# noise-and-ring-modulator-v1_0.net
KiCad netlist of a schematic drawn in EAGLE
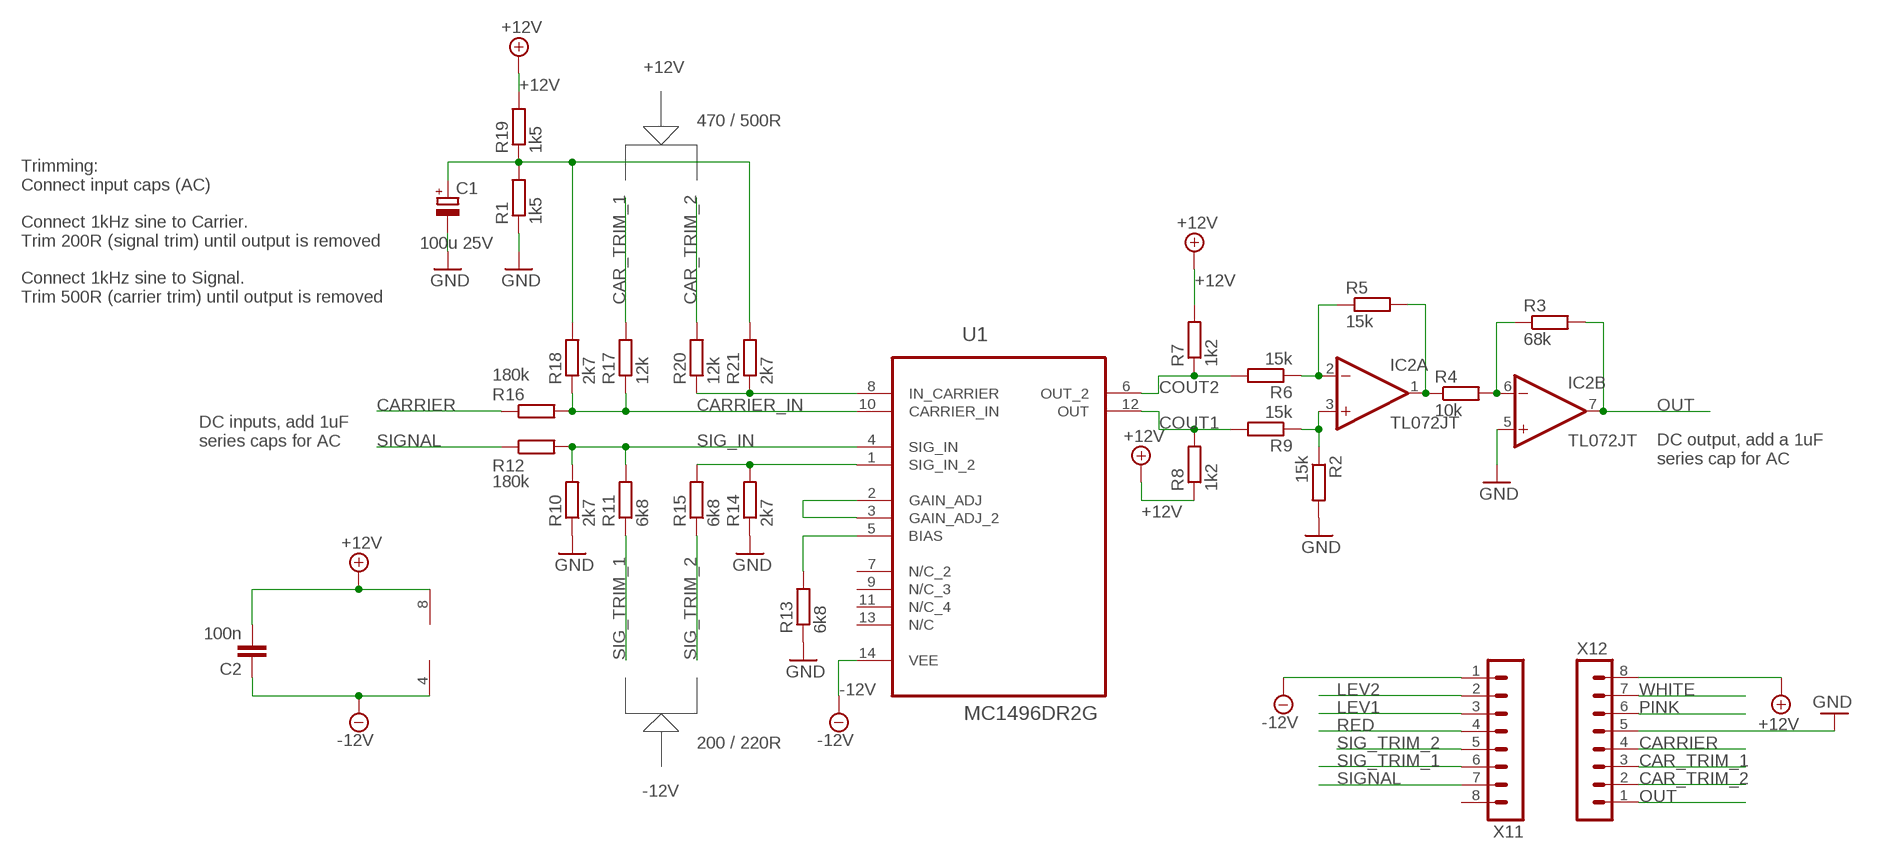
[diagram p0: schematic, sheet 1]
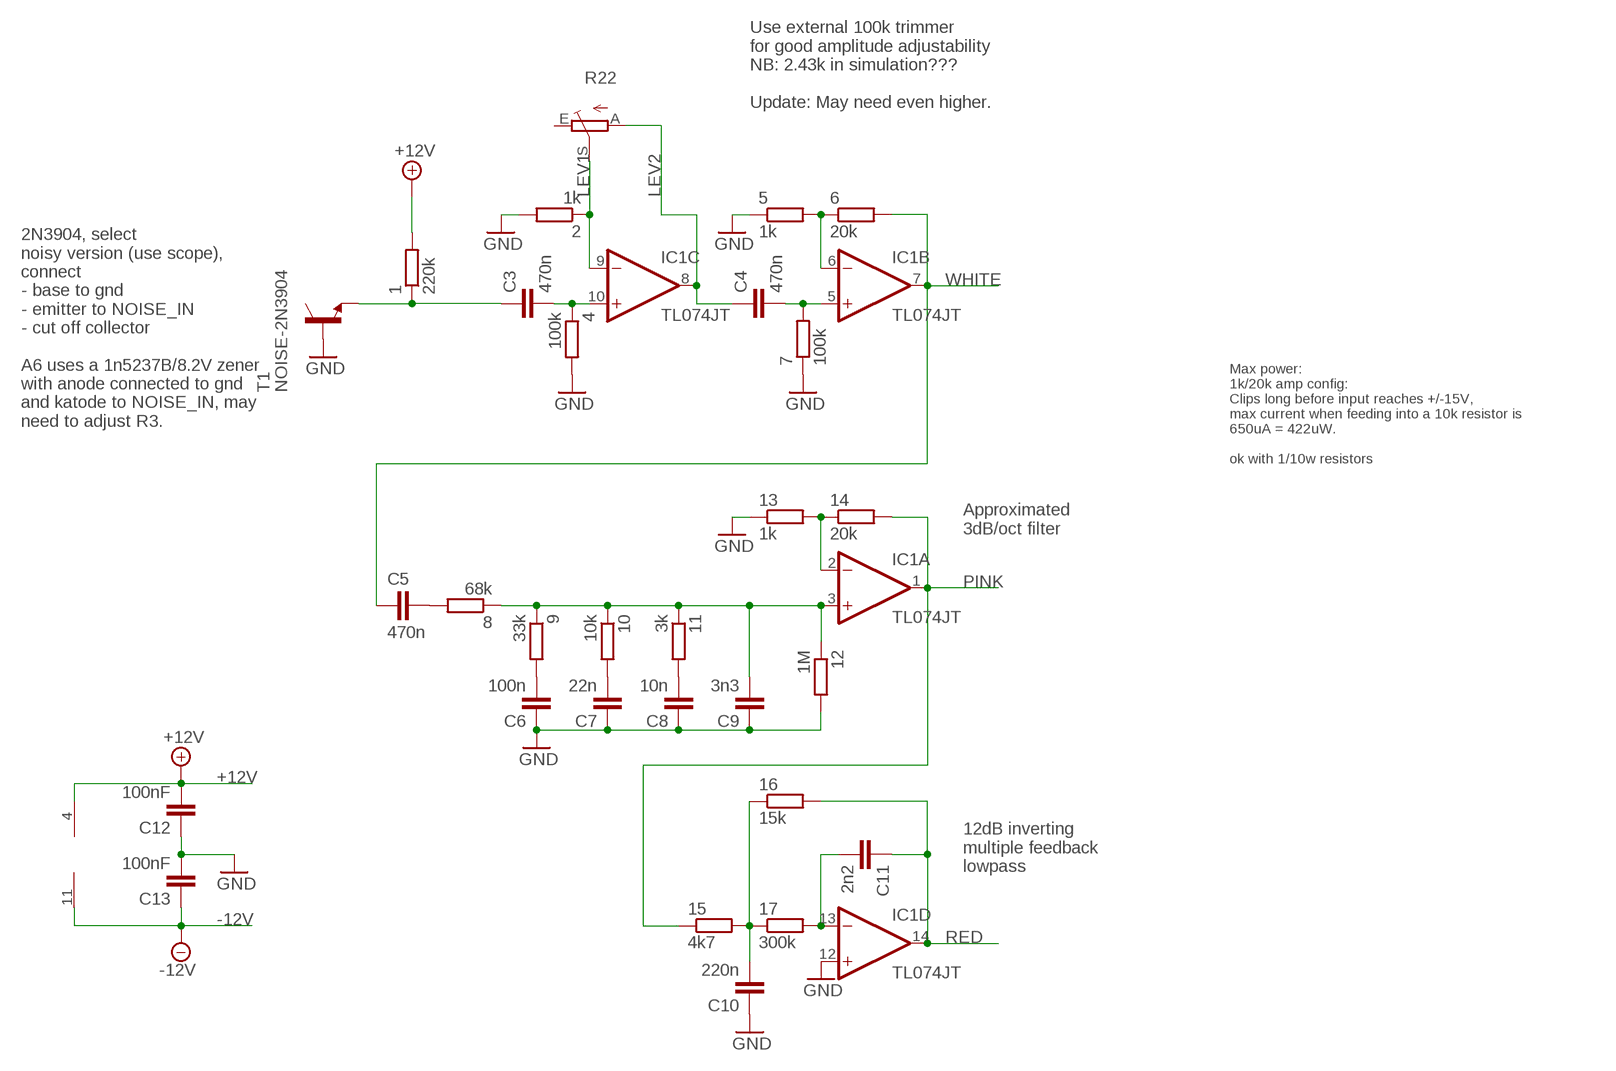
[diagram p1: schematic, sheet 2]

(export (version "E")
  (design (tool "Eeschema 10.0.6"))
  (components
    (comp (ref "1")
      (value "220k")
      (footprint "eagle-import:R0402")
      (libsource (lib "eagle-import") (part "R-EU_R0402"))
    )
    (comp (ref "2")
      (value "1k")
      (footprint "eagle-import:R0402")
      (libsource (lib "eagle-import") (part "R-EU_R0402"))
    )
    (comp (ref "4")
      (value "100k")
      (footprint "eagle-import:R0402")
      (libsource (lib "eagle-import") (part "R-EU_R0402"))
    )
    (comp (ref "5")
      (value "1k")
      (footprint "eagle-import:R0402")
      (libsource (lib "eagle-import") (part "R-EU_R0402"))
    )
    (comp (ref "6")
      (value "20k")
      (footprint "eagle-import:R0402")
      (libsource (lib "eagle-import") (part "R-EU_R0402"))
    )
    (comp (ref "7")
      (value "100k")
      (footprint "eagle-import:R0402")
      (libsource (lib "eagle-import") (part "R-EU_R0402"))
    )
    (comp (ref "8")
      (value "68k")
      (footprint "eagle-import:R0402")
      (libsource (lib "eagle-import") (part "R-EU_R0402"))
    )
    (comp (ref "9")
      (value "33k")
      (footprint "eagle-import:R0402")
      (libsource (lib "eagle-import") (part "R-EU_R0402"))
    )
    (comp (ref "10")
      (value "10k")
      (footprint "eagle-import:R0402")
      (libsource (lib "eagle-import") (part "R-EU_R0402"))
    )
    (comp (ref "11")
      (value "3k")
      (footprint "eagle-import:R0402")
      (libsource (lib "eagle-import") (part "R-EU_R0402"))
    )
    (comp (ref "12")
      (value "1M")
      (footprint "eagle-import:R0402")
      (libsource (lib "eagle-import") (part "R-EU_R0402"))
    )
    (comp (ref "13")
      (value "1k")
      (footprint "eagle-import:R0402")
      (libsource (lib "eagle-import") (part "R-EU_R0402"))
    )
    (comp (ref "14")
      (value "20k")
      (footprint "eagle-import:R0402")
      (libsource (lib "eagle-import") (part "R-EU_R0402"))
    )
    (comp (ref "15")
      (value "4k7")
      (footprint "eagle-import:R0402")
      (libsource (lib "eagle-import") (part "R-EU_R0402"))
    )
    (comp (ref "16")
      (value "15k")
      (footprint "eagle-import:R0402")
      (libsource (lib "eagle-import") (part "R-EU_R0402"))
    )
    (comp (ref "17")
      (value "300k")
      (footprint "eagle-import:R0402")
      (libsource (lib "eagle-import") (part "R-EU_R0402"))
    )
    (comp (ref "C3")
      (value "470n")
      (footprint "eagle-import:C0402-J")
      (libsource (lib "eagle-import") (part "C-EU-J"))
    )
    (comp (ref "C4")
      (value "470n")
      (footprint "eagle-import:C0402-J")
      (libsource (lib "eagle-import") (part "C-EU-J"))
    )
    (comp (ref "C5")
      (value "470n")
      (footprint "eagle-import:C0402-J")
      (libsource (lib "eagle-import") (part "C-EU-J"))
    )
    (comp (ref "C6")
      (value "100n")
      (footprint "eagle-import:C0402-J")
      (libsource (lib "eagle-import") (part "C-EU-J"))
    )
    (comp (ref "C7")
      (value "22n")
      (footprint "eagle-import:C0402-J")
      (libsource (lib "eagle-import") (part "C-EU-J"))
    )
    (comp (ref "C8")
      (value "10n")
      (footprint "eagle-import:C0402-J")
      (libsource (lib "eagle-import") (part "C-EU-J"))
    )
    (comp (ref "C9")
      (value "3n3")
      (footprint "eagle-import:C0402-J")
      (libsource (lib "eagle-import") (part "C-EU-J"))
    )
    (comp (ref "C10")
      (value "220n")
      (footprint "eagle-import:C0402-J")
      (libsource (lib "eagle-import") (part "C-EU-J"))
    )
    (comp (ref "C11")
      (value "2n2")
      (footprint "eagle-import:C0402-J")
      (libsource (lib "eagle-import") (part "C-EU-J"))
    )
    (comp (ref "C12")
      (value "100nF")
      (footprint "eagle-import:C0402-J")
      (libsource (lib "eagle-import") (part "C-EU-J"))
    )
    (comp (ref "C13")
      (value "100nF")
      (footprint "eagle-import:C0402-J")
      (libsource (lib "eagle-import") (part "C-EU-J"))
    )
    (comp (ref "IC1")
      (value "TL074JT")
      (footprint "eagle-import:TSSOP14J")
      (libsource (lib "eagle-import") (part "TL074JT"))
    )
    (comp (ref "R22")
      (value "TRIM_EU-S64W")
      (footprint "eagle-import:S64W")
      (libsource (lib "eagle-import") (part "TRIM_EU-S64W"))
    )
    (comp (ref "T1")
      (value "NOISE-2N3904")
      (footprint "eagle-import:NOISE-2N3904-J")
      (libsource (lib "eagle-import") (part "NOISE-2N3904"))
    )
    (comp (ref "C1")
      (value "100u 25V")
      (footprint "eagle-import:UD-4X5,8_NICHICON")
      (libsource (lib "eagle-import") (part "CPOL-EUUD-4X5,8"))
    )
    (comp (ref "C2")
      (value "100n")
      (footprint "eagle-import:C0402-J")
      (libsource (lib "eagle-import") (part "C-EU-J"))
    )
    (comp (ref "IC2")
      (value "TL072JT")
      (footprint "eagle-import:TSSOP8J")
      (libsource (lib "eagle-import") (part "TL072JT"))
    )
    (comp (ref "R1")
      (value "1k5")
      (footprint "eagle-import:R0402")
      (libsource (lib "eagle-import") (part "R-EU_R0402"))
    )
    (comp (ref "R2")
      (value "15k")
      (footprint "eagle-import:R0402")
      (libsource (lib "eagle-import") (part "R-EU_R0402"))
    )
    (comp (ref "R3")
      (value "68k")
      (footprint "eagle-import:R0402")
      (libsource (lib "eagle-import") (part "R-EU_R0402"))
    )
    (comp (ref "R4")
      (value "10k")
      (footprint "eagle-import:R0402")
      (libsource (lib "eagle-import") (part "R-EU_R0402"))
    )
    (comp (ref "R5")
      (value "15k")
      (footprint "eagle-import:R0402")
      (libsource (lib "eagle-import") (part "R-EU_R0402"))
    )
    (comp (ref "R6")
      (value "15k")
      (footprint "eagle-import:R0402")
      (libsource (lib "eagle-import") (part "R-EU_R0402"))
    )
    (comp (ref "R7")
      (value "1k2")
      (footprint "eagle-import:R0402")
      (libsource (lib "eagle-import") (part "R-EU_R0402"))
    )
    (comp (ref "R8")
      (value "1k2")
      (footprint "eagle-import:R0402")
      (libsource (lib "eagle-import") (part "R-EU_R0402"))
    )
    (comp (ref "R9")
      (value "15k")
      (footprint "eagle-import:R0402")
      (libsource (lib "eagle-import") (part "R-EU_R0402"))
    )
    (comp (ref "R10")
      (value "2k7")
      (footprint "eagle-import:R0402")
      (libsource (lib "eagle-import") (part "R-EU_R0402"))
    )
    (comp (ref "R11")
      (value "6k8")
      (footprint "eagle-import:R0402")
      (libsource (lib "eagle-import") (part "R-EU_R0402"))
    )
    (comp (ref "R12")
      (value "180k")
      (footprint "eagle-import:R0402")
      (libsource (lib "eagle-import") (part "R-EU_R0402"))
    )
    (comp (ref "R13")
      (value "6k8")
      (footprint "eagle-import:R0402")
      (libsource (lib "eagle-import") (part "R-EU_R0402"))
    )
    (comp (ref "R14")
      (value "2k7")
      (footprint "eagle-import:R0402")
      (libsource (lib "eagle-import") (part "R-EU_R0402"))
    )
    (comp (ref "R15")
      (value "6k8")
      (footprint "eagle-import:R0402")
      (libsource (lib "eagle-import") (part "R-EU_R0402"))
    )
    (comp (ref "R16")
      (value "180k")
      (footprint "eagle-import:R0402")
      (libsource (lib "eagle-import") (part "R-EU_R0402"))
    )
    (comp (ref "R17")
      (value "12k")
      (footprint "eagle-import:R0402")
      (libsource (lib "eagle-import") (part "R-EU_R0402"))
    )
    (comp (ref "R18")
      (value "2k7")
      (footprint "eagle-import:R0402")
      (libsource (lib "eagle-import") (part "R-EU_R0402"))
    )
    (comp (ref "R19")
      (value "1k5")
      (footprint "eagle-import:R0402")
      (libsource (lib "eagle-import") (part "R-EU_R0402"))
    )
    (comp (ref "R20")
      (value "12k")
      (footprint "eagle-import:R0402")
      (libsource (lib "eagle-import") (part "R-EU_R0402"))
    )
    (comp (ref "R21")
      (value "2k7")
      (footprint "eagle-import:R0402")
      (libsource (lib "eagle-import") (part "R-EU_R0402"))
    )
    (comp (ref "U1")
      (value "MC1496DR2G")
      (footprint "eagle-import:SOIC127P600X175-14N")
      (libsource (lib "eagle-import") (part "MC1496DR2G"))
    )
    (comp (ref "X11")
      (value "MA08-1JN")
      (footprint "eagle-import:MA08N-1J")
      (libsource (lib "eagle-import") (part "MA08-1JN"))
    )
    (comp (ref "X12")
      (value "MA08-1JN")
      (footprint "eagle-import:MA08N-1J")
      (libsource (lib "eagle-import") (part "MA08-1JN"))
    )
  )
  (nets
    (net (code "1") (name "+12V") (class "Default")
      (node (ref "1") (pin "2") (pinfunction "2_2") (pintype "passive"))
      (node (ref "C12") (pin "2") (pinfunction "2_2") (pintype "passive"))
      (node (ref "C2") (pin "2") (pinfunction "2_2") (pintype "passive"))
      (node (ref "IC1") (pin "4") (pinfunction "V+_4") (pintype "power_in"))
      (node (ref "IC2") (pin "8") (pinfunction "V+_8") (pintype "power_in"))
      (node (ref "R19") (pin "2") (pinfunction "2_2") (pintype "passive"))
      (node (ref "R7") (pin "2") (pinfunction "2_2") (pintype "passive"))
      (node (ref "R8") (pin "1") (pinfunction "1_1") (pintype "passive"))
      (node (ref "X12") (pin "8") (pinfunction "8_8") (pintype "passive"))
    )
    (net (code "2") (name "-12V") (class "Default")
      (node (ref "C13") (pin "1") (pinfunction "1_1") (pintype "passive"))
      (node (ref "C2") (pin "1") (pinfunction "1_1") (pintype "passive"))
      (node (ref "IC1") (pin "11") (pinfunction "V-_11") (pintype "power_in"))
      (node (ref "IC2") (pin "4") (pinfunction "V-_4") (pintype "power_in"))
      (node (ref "U1") (pin "14") (pinfunction "VEE_14") (pintype "passive"))
      (node (ref "X11") (pin "1") (pinfunction "1_1") (pintype "passive"))
    )
    (net (code "3") (name "CARRIER") (class "Default")
      (node (ref "R16") (pin "1") (pinfunction "1_1") (pintype "passive"))
      (node (ref "X12") (pin "4") (pinfunction "4_4") (pintype "passive"))
    )
    (net (code "4") (name "CARRIER_IN") (class "Default")
      (node (ref "R16") (pin "2") (pinfunction "2_2") (pintype "passive"))
      (node (ref "R17") (pin "1") (pinfunction "1_1") (pintype "passive"))
      (node (ref "R18") (pin "1") (pinfunction "1_1") (pintype "passive"))
      (node (ref "U1") (pin "10") (pinfunction "CARRIER_IN_10") (pintype "power_in"))
    )
    (net (code "5") (name "CAR_TRIM_1") (class "Default")
      (node (ref "R17") (pin "2") (pinfunction "2_2") (pintype "passive"))
      (node (ref "X12") (pin "3") (pinfunction "3_3") (pintype "passive"))
    )
    (net (code "6") (name "CAR_TRIM_2") (class "Default")
      (node (ref "R20") (pin "2") (pinfunction "2_2") (pintype "passive"))
      (node (ref "X12") (pin "2") (pinfunction "2_2") (pintype "passive"))
    )
    (net (code "7") (name "COUT1") (class "Default")
      (node (ref "R8") (pin "2") (pinfunction "2_2") (pintype "passive"))
      (node (ref "R9") (pin "2") (pinfunction "2_2") (pintype "passive"))
      (node (ref "U1") (pin "12") (pinfunction "OUT_12") (pintype "output"))
    )
    (net (code "8") (name "COUT2") (class "Default")
      (node (ref "R6") (pin "2") (pinfunction "2_2") (pintype "passive"))
      (node (ref "R7") (pin "1") (pinfunction "1_1") (pintype "passive"))
      (node (ref "U1") (pin "6") (pinfunction "OUT_2_6") (pintype "output"))
    )
    (net (code "9") (name "GND") (class "Default")
      (node (ref "12") (pin "2") (pinfunction "2_2") (pintype "passive"))
      (node (ref "13") (pin "1") (pinfunction "1_1") (pintype "passive"))
      (node (ref "2") (pin "2") (pinfunction "2_2") (pintype "passive"))
      (node (ref "4") (pin "2") (pinfunction "2_2") (pintype "passive"))
      (node (ref "5") (pin "1") (pinfunction "1_1") (pintype "passive"))
      (node (ref "7") (pin "1") (pinfunction "1_1") (pintype "passive"))
      (node (ref "C1") (pin "-") (pinfunction "-_-") (pintype "passive"))
      (node (ref "C10") (pin "1") (pinfunction "1_1") (pintype "passive"))
      (node (ref "C12") (pin "1") (pinfunction "1_1") (pintype "passive"))
      (node (ref "C13") (pin "2") (pinfunction "2_2") (pintype "passive"))
      (node (ref "C6") (pin "1") (pinfunction "1_1") (pintype "passive"))
      (node (ref "C7") (pin "1") (pinfunction "1_1") (pintype "passive"))
      (node (ref "C8") (pin "1") (pinfunction "1_1") (pintype "passive"))
      (node (ref "C9") (pin "1") (pinfunction "1_1") (pintype "passive"))
      (node (ref "IC1") (pin "12") (pinfunction "+IN_12") (pintype "input"))
      (node (ref "IC2") (pin "5") (pinfunction "+IN_5") (pintype "input"))
      (node (ref "R1") (pin "1") (pinfunction "1_1") (pintype "passive"))
      (node (ref "R10") (pin "1") (pinfunction "1_1") (pintype "passive"))
      (node (ref "R13") (pin "1") (pinfunction "1_1") (pintype "passive"))
      (node (ref "R14") (pin "1") (pinfunction "1_1") (pintype "passive"))
      (node (ref "R2") (pin "2") (pinfunction "2_2") (pintype "passive"))
      (node (ref "T1") (pin "B") (pinfunction "B_B") (pintype "passive"))
      (node (ref "X12") (pin "5") (pinfunction "5_5") (pintype "passive"))
    )
    (net (code "10") (name "LEV1") (class "Default")
      (node (ref "2") (pin "1") (pinfunction "1_1") (pintype "passive"))
      (node (ref "IC1") (pin "9") (pinfunction "-IN_9") (pintype "input"))
      (node (ref "R22") (pin "S") (pinfunction "S_S") (pintype "passive"))
      (node (ref "X11") (pin "3") (pinfunction "3_3") (pintype "passive"))
    )
    (net (code "11") (name "LEV2") (class "Default")
      (node (ref "C4") (pin "1") (pinfunction "1_1") (pintype "passive"))
      (node (ref "IC1") (pin "8") (pinfunction "OUT_8") (pintype "output"))
      (node (ref "R22") (pin "A") (pinfunction "A_A") (pintype "passive"))
      (node (ref "X11") (pin "2") (pinfunction "2_2") (pintype "passive"))
    )
    (net (code "12") (name "Net-(1-Pad1)") (class "Default")
      (node (ref "1") (pin "1") (pinfunction "1_1") (pintype "passive"))
      (node (ref "C3") (pin "1") (pinfunction "1_1") (pintype "passive"))
      (node (ref "T1") (pin "E") (pinfunction "E_E") (pintype "passive"))
    )
    (net (code "13") (name "Net-(8-Pad2)") (class "Default")
      (node (ref "8") (pin "2") (pinfunction "2_2") (pintype "passive"))
      (node (ref "C5") (pin "2") (pinfunction "2_2") (pintype "passive"))
    )
    (net (code "14") (name "Net-(9-Pad2)") (class "Default")
      (node (ref "9") (pin "2") (pinfunction "2_2") (pintype "passive"))
      (node (ref "C6") (pin "2") (pinfunction "2_2") (pintype "passive"))
    )
    (net (code "15") (name "Net-(10-Pad2)") (class "Default")
      (node (ref "10") (pin "2") (pinfunction "2_2") (pintype "passive"))
      (node (ref "C7") (pin "2") (pinfunction "2_2") (pintype "passive"))
    )
    (net (code "16") (name "Net-(11-Pad2)") (class "Default")
      (node (ref "11") (pin "2") (pinfunction "2_2") (pintype "passive"))
      (node (ref "C8") (pin "2") (pinfunction "2_2") (pintype "passive"))
    )
    (net (code "17") (name "Net-(15-Pad2)") (class "Default")
      (node (ref "15") (pin "2") (pinfunction "2_2") (pintype "passive"))
      (node (ref "16") (pin "1") (pinfunction "1_1") (pintype "passive"))
      (node (ref "17") (pin "1") (pinfunction "1_1") (pintype "passive"))
      (node (ref "C10") (pin "2") (pinfunction "2_2") (pintype "passive"))
    )
    (net (code "18") (name "Net-(C1-Pad+)") (class "Default")
      (node (ref "C1") (pin "+") (pinfunction "+_+") (pintype "passive"))
      (node (ref "R1") (pin "2") (pinfunction "2_2") (pintype "passive"))
      (node (ref "R18") (pin "2") (pinfunction "2_2") (pintype "passive"))
      (node (ref "R19") (pin "1") (pinfunction "1_1") (pintype "passive"))
      (node (ref "R21") (pin "2") (pinfunction "2_2") (pintype "passive"))
    )
    (net (code "19") (name "Net-(IC1A-+IN)") (class "Default")
      (node (ref "10") (pin "1") (pinfunction "1_1") (pintype "passive"))
      (node (ref "11") (pin "1") (pinfunction "1_1") (pintype "passive"))
      (node (ref "12") (pin "1") (pinfunction "1_1") (pintype "passive"))
      (node (ref "8") (pin "1") (pinfunction "1_1") (pintype "passive"))
      (node (ref "9") (pin "1") (pinfunction "1_1") (pintype "passive"))
      (node (ref "C9") (pin "2") (pinfunction "2_2") (pintype "passive"))
      (node (ref "IC1") (pin "3") (pinfunction "+IN_3") (pintype "input"))
    )
    (net (code "20") (name "Net-(IC1A--IN)") (class "Default")
      (node (ref "13") (pin "2") (pinfunction "2_2") (pintype "passive"))
      (node (ref "14") (pin "1") (pinfunction "1_1") (pintype "passive"))
      (node (ref "IC1") (pin "2") (pinfunction "-IN_2") (pintype "input"))
    )
    (net (code "21") (name "Net-(IC1B-+IN)") (class "Default")
      (node (ref "7") (pin "2") (pinfunction "2_2") (pintype "passive"))
      (node (ref "C4") (pin "2") (pinfunction "2_2") (pintype "passive"))
      (node (ref "IC1") (pin "5") (pinfunction "+IN_5") (pintype "input"))
    )
    (net (code "22") (name "Net-(IC1B--IN)") (class "Default")
      (node (ref "5") (pin "2") (pinfunction "2_2") (pintype "passive"))
      (node (ref "6") (pin "1") (pinfunction "1_1") (pintype "passive"))
      (node (ref "IC1") (pin "6") (pinfunction "-IN_6") (pintype "input"))
    )
    (net (code "23") (name "Net-(IC1C-+IN)") (class "Default")
      (node (ref "4") (pin "1") (pinfunction "1_1") (pintype "passive"))
      (node (ref "C3") (pin "2") (pinfunction "2_2") (pintype "passive"))
      (node (ref "IC1") (pin "10") (pinfunction "+IN_10") (pintype "input"))
    )
    (net (code "24") (name "Net-(IC1D--IN)") (class "Default")
      (node (ref "17") (pin "2") (pinfunction "2_2") (pintype "passive"))
      (node (ref "C11") (pin "2") (pinfunction "2_2") (pintype "passive"))
      (node (ref "IC1") (pin "13") (pinfunction "-IN_13") (pintype "input"))
    )
    (net (code "25") (name "Net-(IC2A-+IN)") (class "Default")
      (node (ref "IC2") (pin "3") (pinfunction "+IN_3") (pintype "input"))
      (node (ref "R2") (pin "1") (pinfunction "1_1") (pintype "passive"))
      (node (ref "R9") (pin "1") (pinfunction "1_1") (pintype "passive"))
    )
    (net (code "26") (name "Net-(IC2A--IN)") (class "Default")
      (node (ref "IC2") (pin "2") (pinfunction "-IN_2") (pintype "input"))
      (node (ref "R5") (pin "1") (pinfunction "1_1") (pintype "passive"))
      (node (ref "R6") (pin "1") (pinfunction "1_1") (pintype "passive"))
    )
    (net (code "27") (name "Net-(IC2A-OUT)") (class "Default")
      (node (ref "IC2") (pin "1") (pinfunction "OUT_1") (pintype "output"))
      (node (ref "R4") (pin "1") (pinfunction "1_1") (pintype "passive"))
      (node (ref "R5") (pin "2") (pinfunction "2_2") (pintype "passive"))
    )
    (net (code "28") (name "Net-(IC2B--IN)") (class "Default")
      (node (ref "IC2") (pin "6") (pinfunction "-IN_6") (pintype "input"))
      (node (ref "R3") (pin "1") (pinfunction "1_1") (pintype "passive"))
      (node (ref "R4") (pin "2") (pinfunction "2_2") (pintype "passive"))
    )
    (net (code "29") (name "Net-(U1-BIAS)") (class "Default")
      (node (ref "R13") (pin "2") (pinfunction "2_2") (pintype "passive"))
      (node (ref "U1") (pin "5") (pinfunction "BIAS_5") (pintype "input"))
    )
    (net (code "30") (name "Net-(U1-GAIN_ADJ)") (class "Default")
      (node (ref "U1") (pin "2") (pinfunction "GAIN_ADJ_2") (pintype "input"))
      (node (ref "U1") (pin "3") (pinfunction "GAIN_ADJ_2_3") (pintype "input"))
    )
    (net (code "31") (name "Net-(U1-IN_CARRIER)") (class "Default")
      (node (ref "R20") (pin "1") (pinfunction "1_1") (pintype "passive"))
      (node (ref "R21") (pin "1") (pinfunction "1_1") (pintype "passive"))
      (node (ref "U1") (pin "8") (pinfunction "IN_CARRIER_8") (pintype "power_in"))
    )
    (net (code "32") (name "Net-(U1-SIG_IN_2)") (class "Default")
      (node (ref "R14") (pin "2") (pinfunction "2_2") (pintype "passive"))
      (node (ref "R15") (pin "2") (pinfunction "2_2") (pintype "passive"))
      (node (ref "U1") (pin "1") (pinfunction "SIG_IN_2_1") (pintype "input"))
    )
    (net (code "33") (name "OUT") (class "Default")
      (node (ref "IC2") (pin "7") (pinfunction "OUT_7") (pintype "output"))
      (node (ref "R3") (pin "2") (pinfunction "2_2") (pintype "passive"))
      (node (ref "X12") (pin "1") (pinfunction "1_1") (pintype "passive"))
    )
    (net (code "34") (name "PINK") (class "Default")
      (node (ref "14") (pin "2") (pinfunction "2_2") (pintype "passive"))
      (node (ref "15") (pin "1") (pinfunction "1_1") (pintype "passive"))
      (node (ref "IC1") (pin "1") (pinfunction "OUT_1") (pintype "output"))
      (node (ref "X12") (pin "6") (pinfunction "6_6") (pintype "passive"))
    )
    (net (code "35") (name "RED") (class "Default")
      (node (ref "16") (pin "2") (pinfunction "2_2") (pintype "passive"))
      (node (ref "C11") (pin "1") (pinfunction "1_1") (pintype "passive"))
      (node (ref "IC1") (pin "14") (pinfunction "OUT_14") (pintype "output"))
      (node (ref "X11") (pin "4") (pinfunction "4_4") (pintype "passive"))
    )
    (net (code "36") (name "SIGNAL") (class "Default")
      (node (ref "R12") (pin "1") (pinfunction "1_1") (pintype "passive"))
      (node (ref "X11") (pin "7") (pinfunction "7_7") (pintype "passive"))
    )
    (net (code "37") (name "SIG_IN") (class "Default")
      (node (ref "R10") (pin "2") (pinfunction "2_2") (pintype "passive"))
      (node (ref "R11") (pin "2") (pinfunction "2_2") (pintype "passive"))
      (node (ref "R12") (pin "2") (pinfunction "2_2") (pintype "passive"))
      (node (ref "U1") (pin "4") (pinfunction "SIG_IN_4") (pintype "input"))
    )
    (net (code "38") (name "SIG_TRIM_1") (class "Default")
      (node (ref "R11") (pin "1") (pinfunction "1_1") (pintype "passive"))
      (node (ref "X11") (pin "6") (pinfunction "6_6") (pintype "passive"))
    )
    (net (code "39") (name "SIG_TRIM_2") (class "Default")
      (node (ref "R15") (pin "1") (pinfunction "1_1") (pintype "passive"))
      (node (ref "X11") (pin "5") (pinfunction "5_5") (pintype "passive"))
    )
    (net (code "40") (name "WHITE") (class "Default")
      (node (ref "6") (pin "2") (pinfunction "2_2") (pintype "passive"))
      (node (ref "C5") (pin "1") (pinfunction "1_1") (pintype "passive"))
      (node (ref "IC1") (pin "7") (pinfunction "OUT_7") (pintype "output"))
      (node (ref "X12") (pin "7") (pinfunction "7_7") (pintype "passive"))
    )
    (net (code "41") (name "unconnected-(R22-PadE)") (class "Default")
      (node (ref "R22") (pin "E") (pinfunction "E_E") (pintype "passive"))
    )
    (net (code "42") (name "unconnected-(U1-N{slash}C-Pad13)") (class "Default")
      (node (ref "U1") (pin "13") (pinfunction "N/C_13") (pintype "no_connect"))
    )
    (net (code "43") (name "unconnected-(U1-N{slash}C_2-Pad7)") (class "Default")
      (node (ref "U1") (pin "7") (pinfunction "N/C_2_7") (pintype "no_connect"))
    )
    (net (code "44") (name "unconnected-(U1-N{slash}C_3-Pad9)") (class "Default")
      (node (ref "U1") (pin "9") (pinfunction "N/C_3_9") (pintype "no_connect"))
    )
    (net (code "45") (name "unconnected-(U1-N{slash}C_4-Pad11)") (class "Default")
      (node (ref "U1") (pin "11") (pinfunction "N/C_4_11") (pintype "no_connect"))
    )
    (net (code "46") (name "unconnected-(X11-Pad8)") (class "Default")
      (node (ref "X11") (pin "8") (pinfunction "8_8") (pintype "passive"))
    )
  )
)
